# xbee-usb.net
KiCad netlist of a schematic drawn in EAGLE
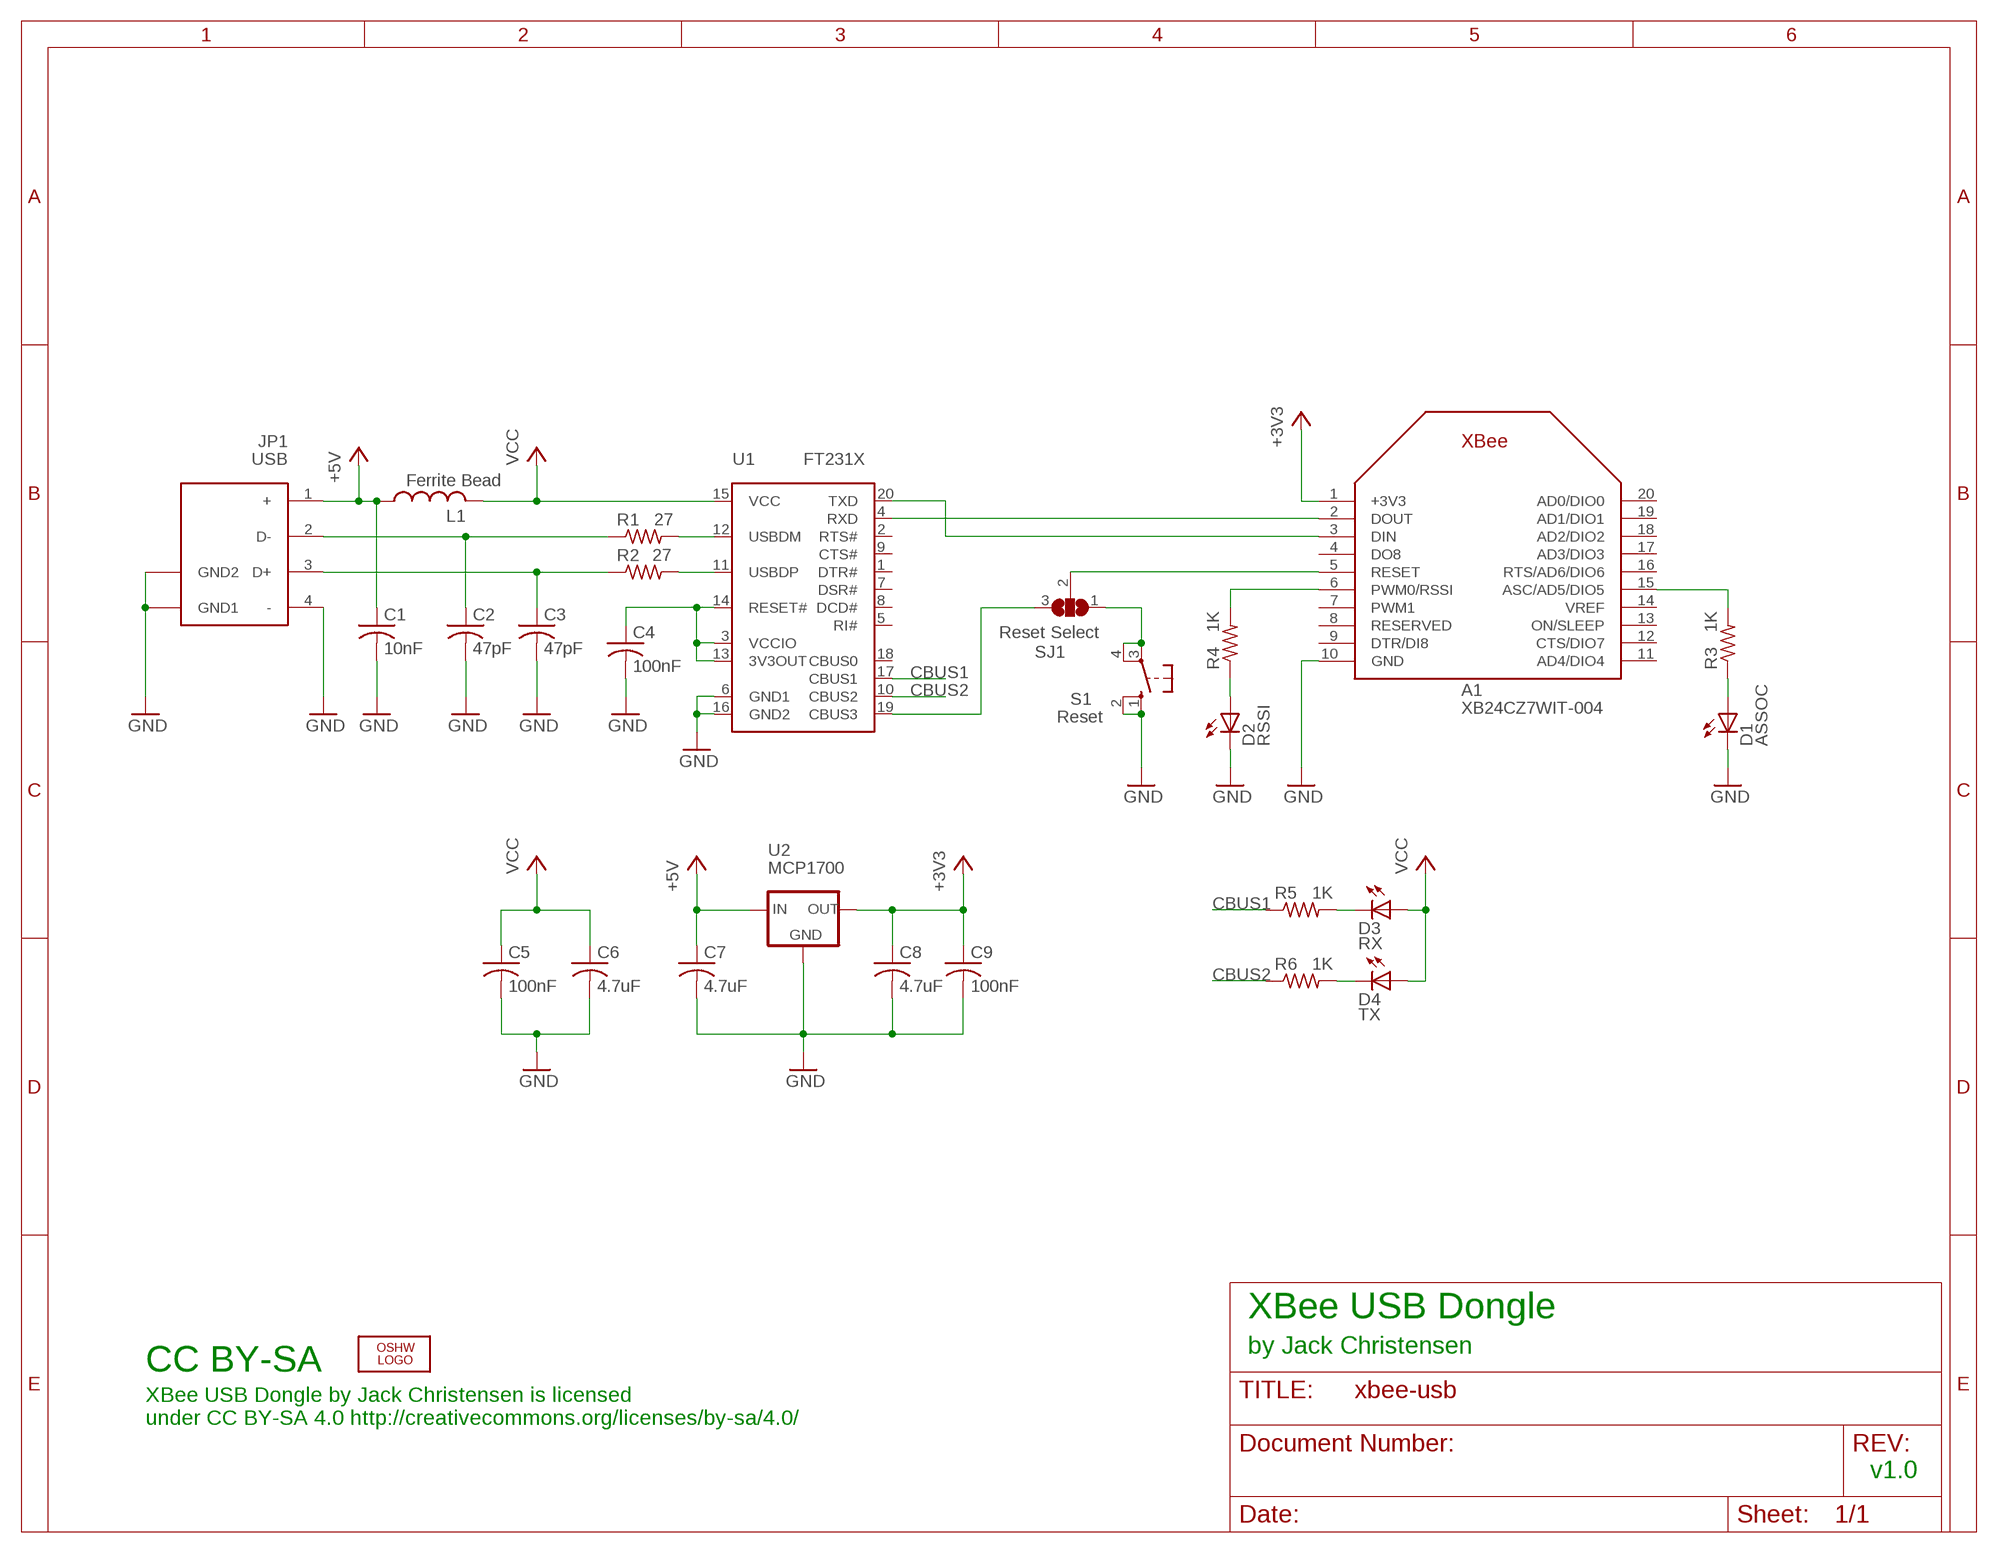
[diagram p0: schematic, sheet 1]

(export (version "E")
  (design (tool "Eeschema 10.0.6"))
  (components
    (comp (ref "A1")
      (value "XB24CZ7WIT-004")
      (footprint "eagle-import:XBEE_OVAL_PADS")
      (libsource (lib "eagle-import") (part "ULINK_XBEEOVALPADS"))
    )
    (comp (ref "C1")
      (value "10nF")
      (footprint "eagle-import:M0805")
      (libsource (lib "eagle-import") (part "C-USM0805"))
    )
    (comp (ref "C2")
      (value "47pF")
      (footprint "eagle-import:M0805")
      (libsource (lib "eagle-import") (part "C-USM0805"))
    )
    (comp (ref "C3")
      (value "47pF")
      (footprint "eagle-import:M0805")
      (libsource (lib "eagle-import") (part "C-USM0805"))
    )
    (comp (ref "C4")
      (value "100nF")
      (footprint "eagle-import:M0805")
      (libsource (lib "eagle-import") (part "C-USM0805"))
    )
    (comp (ref "C5")
      (value "100nF")
      (footprint "eagle-import:M0805")
      (libsource (lib "eagle-import") (part "C-USM0805"))
    )
    (comp (ref "C6")
      (value "4.7uF")
      (footprint "eagle-import:M0805")
      (libsource (lib "eagle-import") (part "C-USM0805"))
    )
    (comp (ref "C7")
      (value "4.7uF")
      (footprint "eagle-import:M0805")
      (libsource (lib "eagle-import") (part "C-USM0805"))
    )
    (comp (ref "C8")
      (value "4.7uF")
      (footprint "eagle-import:M0805")
      (libsource (lib "eagle-import") (part "C-USM0805"))
    )
    (comp (ref "C9")
      (value "100nF")
      (footprint "eagle-import:M0805")
      (libsource (lib "eagle-import") (part "C-USM0805"))
    )
    (comp (ref "D1")
      (value "ASSOC")
      (footprint "eagle-import:D0805")
      (libsource (lib "eagle-import") (part "LEDD0805"))
    )
    (comp (ref "D2")
      (value "RSSI")
      (footprint "eagle-import:D0805A")
      (libsource (lib "eagle-import") (part "LEDD0805A"))
    )
    (comp (ref "D3")
      (value "RX")
      (footprint "eagle-import:D0805")
      (libsource (lib "eagle-import") (part "LEDD0805"))
    )
    (comp (ref "D4")
      (value "TX")
      (footprint "eagle-import:D0805A")
      (libsource (lib "eagle-import") (part "LEDD0805A"))
    )
    (comp (ref "JP1")
      (value "USB")
      (footprint "eagle-import:UP2-AH-X-TH")
      (libsource (lib "eagle-import") (part "UP2-AH-TH"))
    )
    (comp (ref "L1")
      (value "Ferrite Bead")
      (footprint "eagle-import:M0805")
      (libsource (lib "eagle-import") (part "INDUCTORM0805"))
    )
    (comp (ref "LOGO1")
      (value "OSHW_LOGO_8MILX0100-NT")
      (footprint "eagle-import:OSHW_8X100_NOTEXT")
      (libsource (lib "eagle-import") (part "OSHW_LOGO_8MILX0100-NT"))
    )
    (comp (ref "R1")
      (value "27")
      (footprint "eagle-import:M0805")
      (libsource (lib "eagle-import") (part "R-US_M0805"))
    )
    (comp (ref "R2")
      (value "27")
      (footprint "eagle-import:M0805")
      (libsource (lib "eagle-import") (part "R-US_M0805"))
    )
    (comp (ref "R3")
      (value "1K")
      (footprint "eagle-import:M0805")
      (libsource (lib "eagle-import") (part "R-US_M0805"))
    )
    (comp (ref "R4")
      (value "1K")
      (footprint "eagle-import:M0805")
      (libsource (lib "eagle-import") (part "R-US_M0805"))
    )
    (comp (ref "R5")
      (value "1K")
      (footprint "eagle-import:M0805")
      (libsource (lib "eagle-import") (part "R-US_M0805"))
    )
    (comp (ref "R6")
      (value "1K")
      (footprint "eagle-import:M0805")
      (libsource (lib "eagle-import") (part "R-US_M0805"))
    )
    (comp (ref "S1")
      (value "Reset")
      (footprint "eagle-import:B3F-10XXOCT")
      (libsource (lib "eagle-import") (part "10-XXOCT"))
    )
    (comp (ref "SJ1")
      (value "Reset Select")
      (footprint "eagle-import:SJ_2")
      (libsource (lib "eagle-import") (part "SJ2W"))
    )
    (comp (ref "U1")
      (value "FT231X")
      (footprint "eagle-import:SSOP20-W")
      (libsource (lib "eagle-import") (part "FT231XSSOP20-W"))
    )
    (comp (ref "U2")
      (value "MCP1700")
      (footprint "eagle-import:SOT23-W")
      (libsource (lib "eagle-import") (part "MCP1700SOT23-W"))
    )
  )
  (nets
    (net (code "1") (name "+3V3") (class "Default")
      (node (ref "A1") (pin "1") (pinfunction "+3V3_1") (pintype "bidirectional"))
      (node (ref "C8") (pin "1") (pinfunction "1_1") (pintype "passive"))
      (node (ref "C9") (pin "1") (pinfunction "1_1") (pintype "passive"))
      (node (ref "U2") (pin "2") (pinfunction "OUT_2") (pintype "passive"))
    )
    (net (code "2") (name "+5V") (class "Default")
      (node (ref "C1") (pin "1") (pinfunction "1_1") (pintype "passive"))
      (node (ref "C7") (pin "1") (pinfunction "1_1") (pintype "passive"))
      (node (ref "JP1") (pin "1") (pinfunction "+_1") (pintype "bidirectional"))
      (node (ref "L1") (pin "1") (pinfunction "1_1") (pintype "passive"))
      (node (ref "U2") (pin "3") (pinfunction "IN_3") (pintype "input"))
    )
    (net (code "3") (name "/CBUS1") (class "Default")
      (node (ref "R5") (pin "1") (pinfunction "1_1") (pintype "passive"))
      (node (ref "U1") (pin "17") (pinfunction "CBUS1_17") (pintype "bidirectional"))
    )
    (net (code "4") (name "/CBUS2") (class "Default")
      (node (ref "R6") (pin "1") (pinfunction "1_1") (pintype "passive"))
      (node (ref "U1") (pin "10") (pinfunction "CBUS2_10") (pintype "bidirectional"))
    )
    (net (code "5") (name "GND") (class "Default")
      (node (ref "A1") (pin "10") (pinfunction "GND_10") (pintype "power_in"))
      (node (ref "C1") (pin "2") (pinfunction "2_2") (pintype "passive"))
      (node (ref "C2") (pin "2") (pinfunction "2_2") (pintype "passive"))
      (node (ref "C3") (pin "2") (pinfunction "2_2") (pintype "passive"))
      (node (ref "C4") (pin "2") (pinfunction "2_2") (pintype "passive"))
      (node (ref "C5") (pin "2") (pinfunction "2_2") (pintype "passive"))
      (node (ref "C6") (pin "2") (pinfunction "2_2") (pintype "passive"))
      (node (ref "C7") (pin "2") (pinfunction "2_2") (pintype "passive"))
      (node (ref "C8") (pin "2") (pinfunction "2_2") (pintype "passive"))
      (node (ref "C9") (pin "2") (pinfunction "2_2") (pintype "passive"))
      (node (ref "D1") (pin "K") (pinfunction "C_K") (pintype "passive"))
      (node (ref "D2") (pin "K") (pinfunction "C_K") (pintype "passive"))
      (node (ref "JP1") (pin "4") (pinfunction "-_4") (pintype "bidirectional"))
      (node (ref "JP1") (pin "P$5") (pinfunction "GND1_P$5") (pintype "bidirectional"))
      (node (ref "JP1") (pin "P$6") (pinfunction "GND2_P$6") (pintype "bidirectional"))
      (node (ref "S1") (pin "1") (pinfunction "S_1") (pintype "passive"))
      (node (ref "S1") (pin "2") (pinfunction "S1_2") (pintype "passive"))
      (node (ref "U1") (pin "16") (pinfunction "GND2_16") (pintype "bidirectional"))
      (node (ref "U1") (pin "6") (pinfunction "GND1_6") (pintype "bidirectional"))
      (node (ref "U2") (pin "1") (pinfunction "GND_1") (pintype "input"))
    )
    (net (code "6") (name "Net-(A1-ASC{slash}AD5{slash}DIO5)") (class "Default")
      (node (ref "A1") (pin "15") (pinfunction "ASC/AD5/DIO5_15") (pintype "bidirectional"))
      (node (ref "R3") (pin "2") (pinfunction "2_2") (pintype "passive"))
    )
    (net (code "7") (name "Net-(A1-DIN)") (class "Default")
      (node (ref "A1") (pin "3") (pinfunction "DIN_3") (pintype "input"))
      (node (ref "U1") (pin "20") (pinfunction "TXD_20") (pintype "bidirectional"))
    )
    (net (code "8") (name "Net-(A1-DOUT)") (class "Default")
      (node (ref "A1") (pin "2") (pinfunction "DOUT_2") (pintype "output"))
      (node (ref "U1") (pin "4") (pinfunction "RXD_4") (pintype "bidirectional"))
    )
    (net (code "9") (name "Net-(A1-PWM0{slash}RSSI)") (class "Default")
      (node (ref "A1") (pin "6") (pinfunction "PWM0/RSSI_6") (pintype "bidirectional"))
      (node (ref "R4") (pin "2") (pinfunction "2_2") (pintype "passive"))
    )
    (net (code "10") (name "Net-(A1-RESET)") (class "Default")
      (node (ref "A1") (pin "5") (pinfunction "RESET_5") (pintype "bidirectional"))
      (node (ref "SJ1") (pin "2") (pinfunction "2_2") (pintype "passive"))
    )
    (net (code "11") (name "Net-(D1-PadA)") (class "Default")
      (node (ref "D1") (pin "A") (pinfunction "A_A") (pintype "passive"))
      (node (ref "R3") (pin "1") (pinfunction "1_1") (pintype "passive"))
    )
    (net (code "12") (name "Net-(D2-PadA)") (class "Default")
      (node (ref "D2") (pin "A") (pinfunction "A_A") (pintype "passive"))
      (node (ref "R4") (pin "1") (pinfunction "1_1") (pintype "passive"))
    )
    (net (code "13") (name "Net-(D3-C)") (class "Default")
      (node (ref "D3") (pin "K") (pinfunction "C_K") (pintype "passive"))
      (node (ref "R5") (pin "2") (pinfunction "2_2") (pintype "passive"))
    )
    (net (code "14") (name "Net-(D4-C)") (class "Default")
      (node (ref "D4") (pin "K") (pinfunction "C_K") (pintype "passive"))
      (node (ref "R6") (pin "2") (pinfunction "2_2") (pintype "passive"))
    )
    (net (code "15") (name "Net-(JP1-D+)") (class "Default")
      (node (ref "C3") (pin "1") (pinfunction "1_1") (pintype "passive"))
      (node (ref "JP1") (pin "3") (pinfunction "D+_3") (pintype "bidirectional"))
      (node (ref "R2") (pin "1") (pinfunction "1_1") (pintype "passive"))
    )
    (net (code "16") (name "Net-(JP1-D-)") (class "Default")
      (node (ref "C2") (pin "1") (pinfunction "1_1") (pintype "passive"))
      (node (ref "JP1") (pin "2") (pinfunction "D-_2") (pintype "bidirectional"))
      (node (ref "R1") (pin "1") (pinfunction "1_1") (pintype "passive"))
    )
    (net (code "17") (name "Net-(S1-P)") (class "Default")
      (node (ref "S1") (pin "3") (pinfunction "P_3") (pintype "passive"))
      (node (ref "S1") (pin "4") (pinfunction "P1_4") (pintype "passive"))
      (node (ref "SJ1") (pin "1") (pinfunction "1_1") (pintype "passive"))
    )
    (net (code "18") (name "Net-(U1-3V3OUT)") (class "Default")
      (node (ref "C4") (pin "1") (pinfunction "1_1") (pintype "passive"))
      (node (ref "U1") (pin "13") (pinfunction "3V3OUT_13") (pintype "bidirectional"))
      (node (ref "U1") (pin "14") (pinfunction "RESET#_14") (pintype "bidirectional"))
      (node (ref "U1") (pin "3") (pinfunction "VCCIO_3") (pintype "bidirectional"))
    )
    (net (code "19") (name "Net-(U1-CBUS3)") (class "Default")
      (node (ref "SJ1") (pin "3") (pinfunction "3_3") (pintype "passive"))
      (node (ref "U1") (pin "19") (pinfunction "CBUS3_19") (pintype "bidirectional"))
    )
    (net (code "20") (name "Net-(U1-USBDM)") (class "Default")
      (node (ref "R1") (pin "2") (pinfunction "2_2") (pintype "passive"))
      (node (ref "U1") (pin "12") (pinfunction "USBDM_12") (pintype "bidirectional"))
    )
    (net (code "21") (name "Net-(U1-USBDP)") (class "Default")
      (node (ref "R2") (pin "2") (pinfunction "2_2") (pintype "passive"))
      (node (ref "U1") (pin "11") (pinfunction "USBDP_11") (pintype "bidirectional"))
    )
    (net (code "22") (name "VCC") (class "Default")
      (node (ref "C5") (pin "1") (pinfunction "1_1") (pintype "passive"))
      (node (ref "C6") (pin "1") (pinfunction "1_1") (pintype "passive"))
      (node (ref "D3") (pin "A") (pinfunction "A_A") (pintype "passive"))
      (node (ref "D4") (pin "A") (pinfunction "A_A") (pintype "passive"))
      (node (ref "L1") (pin "2") (pinfunction "2_2") (pintype "passive"))
      (node (ref "U1") (pin "15") (pinfunction "VCC_15") (pintype "bidirectional"))
    )
    (net (code "23") (name "unconnected-(A1-AD0{slash}DIO0-Pad20)") (class "Default")
      (node (ref "A1") (pin "20") (pinfunction "AD0/DIO0_20") (pintype "bidirectional"))
    )
    (net (code "24") (name "unconnected-(A1-AD1{slash}DIO1-Pad19)") (class "Default")
      (node (ref "A1") (pin "19") (pinfunction "AD1/DIO1_19") (pintype "bidirectional"))
    )
    (net (code "25") (name "unconnected-(A1-AD2{slash}DIO2-Pad18)") (class "Default")
      (node (ref "A1") (pin "18") (pinfunction "AD2/DIO2_18") (pintype "bidirectional"))
    )
    (net (code "26") (name "unconnected-(A1-AD3{slash}DIO3-Pad17)") (class "Default")
      (node (ref "A1") (pin "17") (pinfunction "AD3/DIO3_17") (pintype "bidirectional"))
    )
    (net (code "27") (name "unconnected-(A1-AD4{slash}DIO4-Pad11)") (class "Default")
      (node (ref "A1") (pin "11") (pinfunction "AD4/DIO4_11") (pintype "bidirectional"))
    )
    (net (code "28") (name "unconnected-(A1-CTS{slash}DIO7-Pad12)") (class "Default")
      (node (ref "A1") (pin "12") (pinfunction "CTS/DIO7_12") (pintype "bidirectional"))
    )
    (net (code "29") (name "unconnected-(A1-DO8-Pad4)") (class "Default")
      (node (ref "A1") (pin "4") (pinfunction "DO8_4") (pintype "output"))
    )
    (net (code "30") (name "unconnected-(A1-DTR{slash}DI8-Pad9)") (class "Default")
      (node (ref "A1") (pin "9") (pinfunction "DTR/DI8_9") (pintype "bidirectional"))
    )
    (net (code "31") (name "unconnected-(A1-ON{slash}SLEEP-Pad13)") (class "Default")
      (node (ref "A1") (pin "13") (pinfunction "ON/SLEEP_13") (pintype "output"))
    )
    (net (code "32") (name "unconnected-(A1-PWM1-Pad7)") (class "Default")
      (node (ref "A1") (pin "7") (pinfunction "PWM1_7") (pintype "bidirectional"))
    )
    (net (code "33") (name "unconnected-(A1-RESERVED-Pad8)") (class "Default")
      (node (ref "A1") (pin "8") (pinfunction "RESERVED_8") (pintype "no_connect"))
    )
    (net (code "34") (name "unconnected-(A1-RTS{slash}AD6{slash}DIO6-Pad16)") (class "Default")
      (node (ref "A1") (pin "16") (pinfunction "RTS/AD6/DIO6_16") (pintype "bidirectional"))
    )
    (net (code "35") (name "unconnected-(A1-VREF-Pad14)") (class "Default")
      (node (ref "A1") (pin "14") (pinfunction "VREF_14") (pintype "bidirectional"))
    )
    (net (code "36") (name "unconnected-(U1-CBUS0-Pad18)") (class "Default")
      (node (ref "U1") (pin "18") (pinfunction "CBUS0_18") (pintype "bidirectional"))
    )
    (net (code "37") (name "unconnected-(U1-CTS#-Pad9)") (class "Default")
      (node (ref "U1") (pin "9") (pinfunction "CTS#_9") (pintype "bidirectional"))
    )
    (net (code "38") (name "unconnected-(U1-DCD#-Pad8)") (class "Default")
      (node (ref "U1") (pin "8") (pinfunction "DCD#_8") (pintype "bidirectional"))
    )
    (net (code "39") (name "unconnected-(U1-DSR#-Pad7)") (class "Default")
      (node (ref "U1") (pin "7") (pinfunction "DSR#_7") (pintype "bidirectional"))
    )
    (net (code "40") (name "unconnected-(U1-DTR#-Pad1)") (class "Default")
      (node (ref "U1") (pin "1") (pinfunction "DTR#_1") (pintype "bidirectional"))
    )
    (net (code "41") (name "unconnected-(U1-RI#-Pad5)") (class "Default")
      (node (ref "U1") (pin "5") (pinfunction "RI#_5") (pintype "bidirectional"))
    )
    (net (code "42") (name "unconnected-(U1-RTS#-Pad2)") (class "Default")
      (node (ref "U1") (pin "2") (pinfunction "RTS#_2") (pintype "bidirectional"))
    )
  )
)
